# Interface.net
KiCad netlist of a schematic drawn in Altium Designer
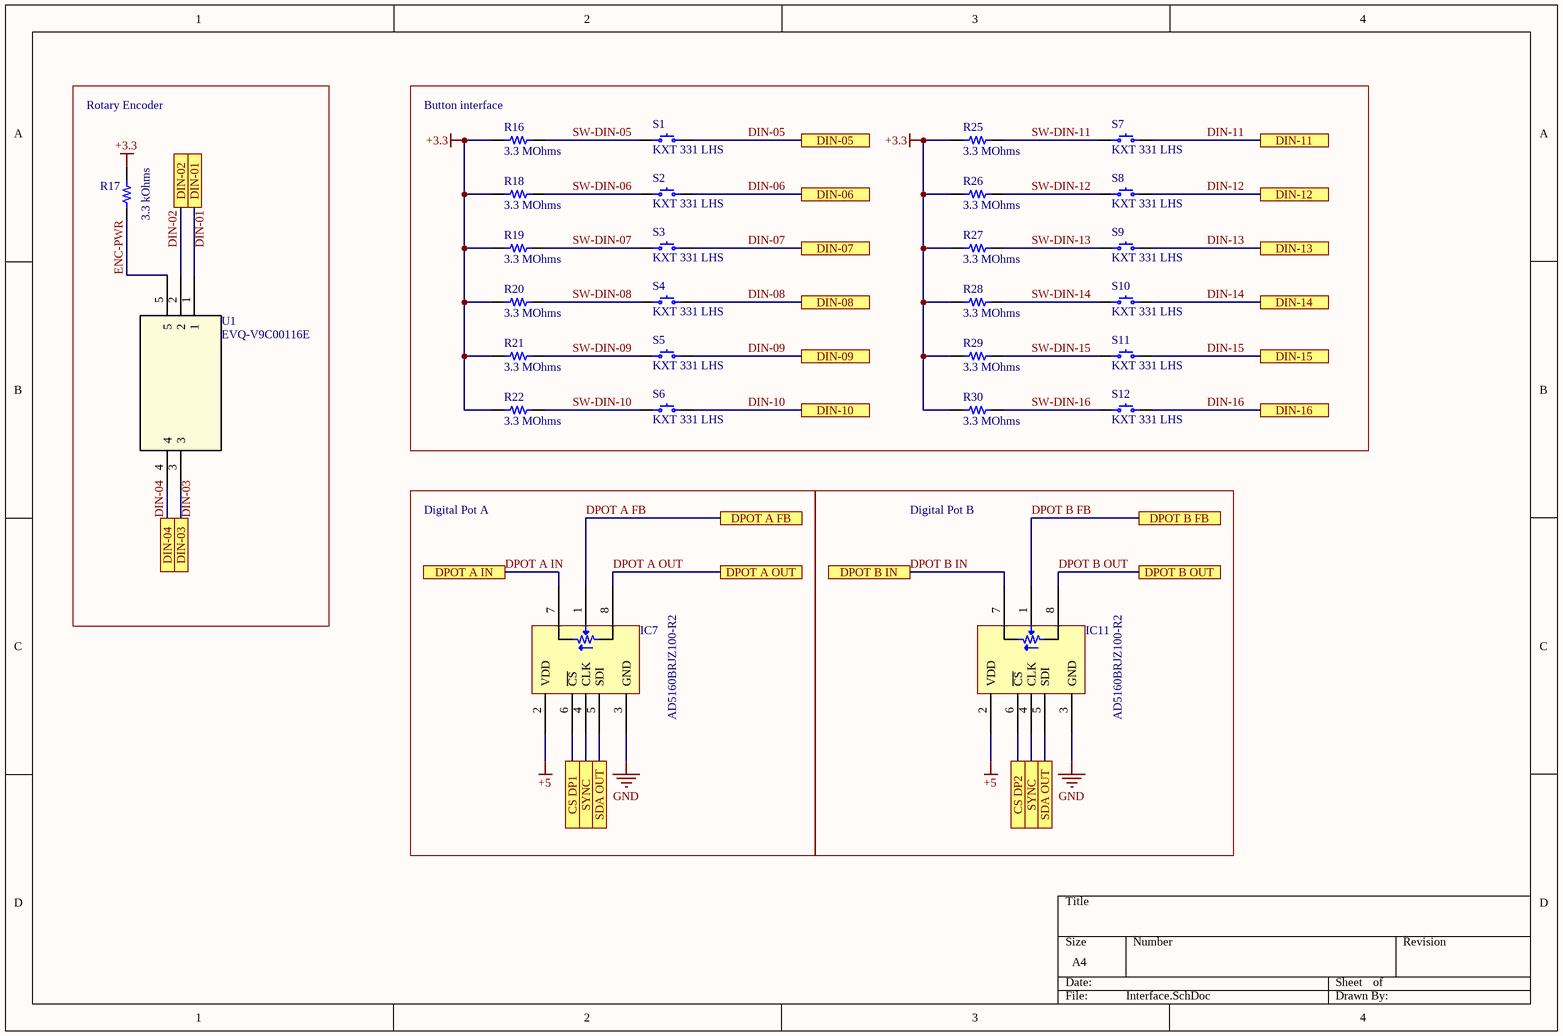
[diagram p0: Interface.SchDoc]

(export (version "E")
  (design (tool "Eeschema 10.0.6"))
  (components
    (comp (ref "IC7")
      (value "AD5160BRJZ100-R2")
      (footprint "ANALOG SOT-23-8 RJ-8")
      (description "IC DGTL POT 100KOHM 256TAP SOT23")
      (fields (field (name "MANUFACTURER") "Analog Devices Inc.") (field (name "TOLERANCE") "±15%"))
      (libsource (lib "Celestial Altium Library - altium_library(1)") (part "ANALOG AD5160"))
    )
    (comp (ref "IC11")
      (value "AD5160BRJZ100-R2")
      (footprint "ANALOG SOT-23-8 RJ-8")
      (description "IC DGTL POT 100KOHM 256TAP SOT23")
      (fields (field (name "MANUFACTURER") "Analog Devices Inc.") (field (name "TOLERANCE") "±15%"))
      (libsource (lib "Celestial Altium Library - altium_library(1)") (part "ANALOG AD5160"))
    )
    (comp (ref "R16")
      (value "3.3 MOhms")
      (footprint "RES 1206_3216")
      (description "RES 3.3M OHM 0.1% 1/4W 1206")
      (fields (field (name "PART NUMBER") "RG3216P-3304-B-T1") (field (name "MANUFACTURER") "Susumu"))
      (libsource (lib "Celestial Altium Library - altium_library(1)") (part "Resistor"))
    )
    (comp (ref "R17")
      (value "3.3 kOhms")
      (footprint "RES 1206_3216")
      (description "RES SMD 3.3K OHM 0.1% 1/4W 1206")
      (fields
        (field (name "PART NUMBER") "ERA-8APB332V")
        (field (name "MANUFACTURER") "Panasonic Electronic Components")
      )
      (libsource (lib "Celestial Altium Library - altium_library(1)") (part "Resistor"))
    )
    (comp (ref "R18")
      (value "3.3 MOhms")
      (footprint "RES 1206_3216")
      (description "RES 3.3M OHM 0.1% 1/4W 1206")
      (fields (field (name "PART NUMBER") "RG3216P-3304-B-T1") (field (name "MANUFACTURER") "Susumu"))
      (libsource (lib "Celestial Altium Library - altium_library(1)") (part "Resistor"))
    )
    (comp (ref "R19")
      (value "3.3 MOhms")
      (footprint "RES 1206_3216")
      (description "RES 3.3M OHM 0.1% 1/4W 1206")
      (fields (field (name "PART NUMBER") "RG3216P-3304-B-T1") (field (name "MANUFACTURER") "Susumu"))
      (libsource (lib "Celestial Altium Library - altium_library(1)") (part "Resistor"))
    )
    (comp (ref "R20")
      (value "3.3 MOhms")
      (footprint "RES 1206_3216")
      (description "RES 3.3M OHM 0.1% 1/4W 1206")
      (fields (field (name "PART NUMBER") "RG3216P-3304-B-T1") (field (name "MANUFACTURER") "Susumu"))
      (libsource (lib "Celestial Altium Library - altium_library(1)") (part "Resistor"))
    )
    (comp (ref "R21")
      (value "3.3 MOhms")
      (footprint "RES 1206_3216")
      (description "RES 3.3M OHM 0.1% 1/4W 1206")
      (fields (field (name "PART NUMBER") "RG3216P-3304-B-T1") (field (name "MANUFACTURER") "Susumu"))
      (libsource (lib "Celestial Altium Library - altium_library(1)") (part "Resistor"))
    )
    (comp (ref "R22")
      (value "3.3 MOhms")
      (footprint "RES 1206_3216")
      (description "RES 3.3M OHM 0.1% 1/4W 1206")
      (fields (field (name "PART NUMBER") "RG3216P-3304-B-T1") (field (name "MANUFACTURER") "Susumu"))
      (libsource (lib "Celestial Altium Library - altium_library(1)") (part "Resistor"))
    )
    (comp (ref "R25")
      (value "3.3 MOhms")
      (footprint "RES 1206_3216")
      (description "RES 3.3M OHM 0.1% 1/4W 1206")
      (fields (field (name "PART NUMBER") "RG3216P-3304-B-T1") (field (name "MANUFACTURER") "Susumu"))
      (libsource (lib "Celestial Altium Library - altium_library(1)") (part "Resistor"))
    )
    (comp (ref "R26")
      (value "3.3 MOhms")
      (footprint "RES 1206_3216")
      (description "RES 3.3M OHM 0.1% 1/4W 1206")
      (fields (field (name "PART NUMBER") "RG3216P-3304-B-T1") (field (name "MANUFACTURER") "Susumu"))
      (libsource (lib "Celestial Altium Library - altium_library(1)") (part "Resistor"))
    )
    (comp (ref "R27")
      (value "3.3 MOhms")
      (footprint "RES 1206_3216")
      (description "RES 3.3M OHM 0.1% 1/4W 1206")
      (fields (field (name "PART NUMBER") "RG3216P-3304-B-T1") (field (name "MANUFACTURER") "Susumu"))
      (libsource (lib "Celestial Altium Library - altium_library(1)") (part "Resistor"))
    )
    (comp (ref "R28")
      (value "3.3 MOhms")
      (footprint "RES 1206_3216")
      (description "RES 3.3M OHM 0.1% 1/4W 1206")
      (fields (field (name "PART NUMBER") "RG3216P-3304-B-T1") (field (name "MANUFACTURER") "Susumu"))
      (libsource (lib "Celestial Altium Library - altium_library(1)") (part "Resistor"))
    )
    (comp (ref "R29")
      (value "3.3 MOhms")
      (footprint "RES 1206_3216")
      (description "RES 3.3M OHM 0.1% 1/4W 1206")
      (fields (field (name "PART NUMBER") "RG3216P-3304-B-T1") (field (name "MANUFACTURER") "Susumu"))
      (libsource (lib "Celestial Altium Library - altium_library(1)") (part "Resistor"))
    )
    (comp (ref "R30")
      (value "3.3 MOhms")
      (footprint "RES 1206_3216")
      (description "RES 3.3M OHM 0.1% 1/4W 1206")
      (fields (field (name "PART NUMBER") "RG3216P-3304-B-T1") (field (name "MANUFACTURER") "Susumu"))
      (libsource (lib "Celestial Altium Library - altium_library(1)") (part "Resistor"))
    )
    (comp (ref "S1")
      (value "KXT 331 LHS")
      (footprint "C&K KXT3")
      (description "SWITCH TACTILE SPST-NO 0.02A 15V")
      (fields (field (name "MANUFACTURER") "C&K"))
      (libsource (lib "Celestial Altium Library - altium_library(1)") (part "SPST-NO 2 PIN"))
    )
    (comp (ref "S2")
      (value "KXT 331 LHS")
      (footprint "C&K KXT3")
      (description "SWITCH TACTILE SPST-NO 0.02A 15V")
      (fields (field (name "MANUFACTURER") "C&K"))
      (libsource (lib "Celestial Altium Library - altium_library(1)") (part "SPST-NO 2 PIN"))
    )
    (comp (ref "S3")
      (value "KXT 331 LHS")
      (footprint "C&K KXT3")
      (description "SWITCH TACTILE SPST-NO 0.02A 15V")
      (fields (field (name "MANUFACTURER") "C&K"))
      (libsource (lib "Celestial Altium Library - altium_library(1)") (part "SPST-NO 2 PIN"))
    )
    (comp (ref "S4")
      (value "KXT 331 LHS")
      (footprint "C&K KXT3")
      (description "SWITCH TACTILE SPST-NO 0.02A 15V")
      (fields (field (name "MANUFACTURER") "C&K"))
      (libsource (lib "Celestial Altium Library - altium_library(1)") (part "SPST-NO 2 PIN"))
    )
    (comp (ref "S5")
      (value "KXT 331 LHS")
      (footprint "C&K KXT3")
      (description "SWITCH TACTILE SPST-NO 0.02A 15V")
      (fields (field (name "MANUFACTURER") "C&K"))
      (libsource (lib "Celestial Altium Library - altium_library(1)") (part "SPST-NO 2 PIN"))
    )
    (comp (ref "S6")
      (value "KXT 331 LHS")
      (footprint "C&K KXT3")
      (description "SWITCH TACTILE SPST-NO 0.02A 15V")
      (fields (field (name "MANUFACTURER") "C&K"))
      (libsource (lib "Celestial Altium Library - altium_library(1)") (part "SPST-NO 2 PIN"))
    )
    (comp (ref "S7")
      (value "KXT 331 LHS")
      (footprint "C&K KXT3")
      (description "SWITCH TACTILE SPST-NO 0.02A 15V")
      (fields (field (name "MANUFACTURER") "C&K"))
      (libsource (lib "Celestial Altium Library - altium_library(1)") (part "SPST-NO 2 PIN"))
    )
    (comp (ref "S8")
      (value "KXT 331 LHS")
      (footprint "C&K KXT3")
      (description "SWITCH TACTILE SPST-NO 0.02A 15V")
      (fields (field (name "MANUFACTURER") "C&K"))
      (libsource (lib "Celestial Altium Library - altium_library(1)") (part "SPST-NO 2 PIN"))
    )
    (comp (ref "S9")
      (value "KXT 331 LHS")
      (footprint "C&K KXT3")
      (description "SWITCH TACTILE SPST-NO 0.02A 15V")
      (fields (field (name "MANUFACTURER") "C&K"))
      (libsource (lib "Celestial Altium Library - altium_library(1)") (part "SPST-NO 2 PIN"))
    )
    (comp (ref "S10")
      (value "KXT 331 LHS")
      (footprint "C&K KXT3")
      (description "SWITCH TACTILE SPST-NO 0.02A 15V")
      (fields (field (name "MANUFACTURER") "C&K"))
      (libsource (lib "Celestial Altium Library - altium_library(1)") (part "SPST-NO 2 PIN"))
    )
    (comp (ref "S11")
      (value "KXT 331 LHS")
      (footprint "C&K KXT3")
      (description "SWITCH TACTILE SPST-NO 0.02A 15V")
      (fields (field (name "MANUFACTURER") "C&K"))
      (libsource (lib "Celestial Altium Library - altium_library(1)") (part "SPST-NO 2 PIN"))
    )
    (comp (ref "S12")
      (value "KXT 331 LHS")
      (footprint "C&K KXT3")
      (description "SWITCH TACTILE SPST-NO 0.02A 15V")
      (fields (field (name "MANUFACTURER") "C&K"))
      (libsource (lib "Celestial Altium Library - altium_library(1)") (part "SPST-NO 2 PIN"))
    )
    (comp (ref "U1")
      (value "EVQ-V9C00116E")
      (footprint "SW_EVQ-V9C00116E_PAN")
      (description "No Description Available")
      (libsource (lib "EVQ-V9C00116E") (part "EVQ-V9C00116E"))
    )
  )
  (nets
    (net (code "1") (name "+3.3") (class "Default")
      (node (ref "R16") (pin "1") (pinfunction "1_1") (pintype "passive"))
      (node (ref "R17") (pin "2") (pinfunction "2_2") (pintype "passive"))
      (node (ref "R18") (pin "1") (pinfunction "1_1") (pintype "passive"))
      (node (ref "R19") (pin "1") (pinfunction "1_1") (pintype "passive"))
      (node (ref "R20") (pin "1") (pinfunction "1_1") (pintype "passive"))
      (node (ref "R21") (pin "1") (pinfunction "1_1") (pintype "passive"))
      (node (ref "R22") (pin "1") (pinfunction "1_1") (pintype "passive"))
      (node (ref "R25") (pin "1") (pinfunction "1_1") (pintype "passive"))
      (node (ref "R26") (pin "1") (pinfunction "1_1") (pintype "passive"))
      (node (ref "R27") (pin "1") (pinfunction "1_1") (pintype "passive"))
      (node (ref "R28") (pin "1") (pinfunction "1_1") (pintype "passive"))
      (node (ref "R29") (pin "1") (pinfunction "1_1") (pintype "passive"))
      (node (ref "R30") (pin "1") (pinfunction "1_1") (pintype "passive"))
    )
    (net (code "2") (name "+5") (class "Default")
      (node (ref "IC11") (pin "2") (pinfunction "VDD_2") (pintype "passive"))
      (node (ref "IC7") (pin "2") (pinfunction "VDD_2") (pintype "passive"))
    )
    (net (code "3") (name "/CS DP1") (class "Default")
      (node (ref "IC7") (pin "6") (pinfunction "~{CS}_6") (pintype "passive"))
    )
    (net (code "4") (name "/CS DP2") (class "Default")
      (node (ref "IC11") (pin "6") (pinfunction "~{CS}_6") (pintype "passive"))
    )
    (net (code "5") (name "/DIN-01") (class "Default")
      (node (ref "U1") (pin "1") (pinfunction "1_1") (pintype "passive"))
    )
    (net (code "6") (name "/DIN-02") (class "Default")
      (node (ref "U1") (pin "2") (pinfunction "2_2") (pintype "passive"))
    )
    (net (code "7") (name "/DIN-03") (class "Default")
      (node (ref "U1") (pin "3") (pinfunction "3_3") (pintype "passive"))
    )
    (net (code "8") (name "/DIN-04") (class "Default")
      (node (ref "U1") (pin "4") (pinfunction "4_4") (pintype "passive"))
    )
    (net (code "9") (name "/DIN-05") (class "Default")
      (node (ref "S1") (pin "2") (pinfunction "2_2") (pintype "passive"))
    )
    (net (code "10") (name "/DIN-06") (class "Default")
      (node (ref "S2") (pin "2") (pinfunction "2_2") (pintype "passive"))
    )
    (net (code "11") (name "/DIN-07") (class "Default")
      (node (ref "S3") (pin "2") (pinfunction "2_2") (pintype "passive"))
    )
    (net (code "12") (name "/DIN-08") (class "Default")
      (node (ref "S4") (pin "2") (pinfunction "2_2") (pintype "passive"))
    )
    (net (code "13") (name "/DIN-09") (class "Default")
      (node (ref "S5") (pin "2") (pinfunction "2_2") (pintype "passive"))
    )
    (net (code "14") (name "/DIN-10") (class "Default")
      (node (ref "S6") (pin "2") (pinfunction "2_2") (pintype "passive"))
    )
    (net (code "15") (name "/DIN-11") (class "Default")
      (node (ref "S7") (pin "2") (pinfunction "2_2") (pintype "passive"))
    )
    (net (code "16") (name "/DIN-12") (class "Default")
      (node (ref "S8") (pin "2") (pinfunction "2_2") (pintype "passive"))
    )
    (net (code "17") (name "/DIN-13") (class "Default")
      (node (ref "S9") (pin "2") (pinfunction "2_2") (pintype "passive"))
    )
    (net (code "18") (name "/DIN-14") (class "Default")
      (node (ref "S10") (pin "2") (pinfunction "2_2") (pintype "passive"))
    )
    (net (code "19") (name "/DIN-15") (class "Default")
      (node (ref "S11") (pin "2") (pinfunction "2_2") (pintype "passive"))
    )
    (net (code "20") (name "/DIN-16") (class "Default")
      (node (ref "S12") (pin "2") (pinfunction "2_2") (pintype "passive"))
    )
    (net (code "21") (name "/DPOT A FB") (class "Default")
      (node (ref "IC7") (pin "1") (pinfunction "W_1") (pintype "passive"))
    )
    (net (code "22") (name "/DPOT A IN") (class "Default")
      (node (ref "IC7") (pin "7") (pinfunction "A_7") (pintype "passive"))
    )
    (net (code "23") (name "/DPOT A OUT") (class "Default")
      (node (ref "IC7") (pin "8") (pinfunction "B_8") (pintype "passive"))
    )
    (net (code "24") (name "/DPOT B FB") (class "Default")
      (node (ref "IC11") (pin "1") (pinfunction "W_1") (pintype "passive"))
    )
    (net (code "25") (name "/DPOT B IN") (class "Default")
      (node (ref "IC11") (pin "7") (pinfunction "A_7") (pintype "passive"))
    )
    (net (code "26") (name "/DPOT B OUT") (class "Default")
      (node (ref "IC11") (pin "8") (pinfunction "B_8") (pintype "passive"))
    )
    (net (code "27") (name "/ENC-PWR") (class "Default")
      (node (ref "R17") (pin "1") (pinfunction "1_1") (pintype "passive"))
      (node (ref "U1") (pin "5") (pinfunction "5_5") (pintype "passive"))
    )
    (net (code "28") (name "/SDA OUT") (class "Default")
      (node (ref "IC11") (pin "5") (pinfunction "SDI_5") (pintype "passive"))
      (node (ref "IC7") (pin "5") (pinfunction "SDI_5") (pintype "passive"))
    )
    (net (code "29") (name "/SW-DIN-05") (class "Default")
      (node (ref "R16") (pin "2") (pinfunction "2_2") (pintype "passive"))
      (node (ref "S1") (pin "1") (pinfunction "1_1") (pintype "passive"))
    )
    (net (code "30") (name "/SW-DIN-06") (class "Default")
      (node (ref "R18") (pin "2") (pinfunction "2_2") (pintype "passive"))
      (node (ref "S2") (pin "1") (pinfunction "1_1") (pintype "passive"))
    )
    (net (code "31") (name "/SW-DIN-07") (class "Default")
      (node (ref "R19") (pin "2") (pinfunction "2_2") (pintype "passive"))
      (node (ref "S3") (pin "1") (pinfunction "1_1") (pintype "passive"))
    )
    (net (code "32") (name "/SW-DIN-08") (class "Default")
      (node (ref "R20") (pin "2") (pinfunction "2_2") (pintype "passive"))
      (node (ref "S4") (pin "1") (pinfunction "1_1") (pintype "passive"))
    )
    (net (code "33") (name "/SW-DIN-09") (class "Default")
      (node (ref "R21") (pin "2") (pinfunction "2_2") (pintype "passive"))
      (node (ref "S5") (pin "1") (pinfunction "1_1") (pintype "passive"))
    )
    (net (code "34") (name "/SW-DIN-10") (class "Default")
      (node (ref "R22") (pin "2") (pinfunction "2_2") (pintype "passive"))
      (node (ref "S6") (pin "1") (pinfunction "1_1") (pintype "passive"))
    )
    (net (code "35") (name "/SW-DIN-11") (class "Default")
      (node (ref "R25") (pin "2") (pinfunction "2_2") (pintype "passive"))
      (node (ref "S7") (pin "1") (pinfunction "1_1") (pintype "passive"))
    )
    (net (code "36") (name "/SW-DIN-12") (class "Default")
      (node (ref "R26") (pin "2") (pinfunction "2_2") (pintype "passive"))
      (node (ref "S8") (pin "1") (pinfunction "1_1") (pintype "passive"))
    )
    (net (code "37") (name "/SW-DIN-13") (class "Default")
      (node (ref "R27") (pin "2") (pinfunction "2_2") (pintype "passive"))
      (node (ref "S9") (pin "1") (pinfunction "1_1") (pintype "passive"))
    )
    (net (code "38") (name "/SW-DIN-14") (class "Default")
      (node (ref "R28") (pin "2") (pinfunction "2_2") (pintype "passive"))
      (node (ref "S10") (pin "1") (pinfunction "1_1") (pintype "passive"))
    )
    (net (code "39") (name "/SW-DIN-15") (class "Default")
      (node (ref "R29") (pin "2") (pinfunction "2_2") (pintype "passive"))
      (node (ref "S11") (pin "1") (pinfunction "1_1") (pintype "passive"))
    )
    (net (code "40") (name "/SW-DIN-16") (class "Default")
      (node (ref "R30") (pin "2") (pinfunction "2_2") (pintype "passive"))
      (node (ref "S12") (pin "1") (pinfunction "1_1") (pintype "passive"))
    )
    (net (code "41") (name "/SYNC") (class "Default")
      (node (ref "IC11") (pin "4") (pinfunction "CLK_4") (pintype "passive"))
      (node (ref "IC7") (pin "4") (pinfunction "CLK_4") (pintype "passive"))
    )
    (net (code "42") (name "GND") (class "Default")
      (node (ref "IC11") (pin "3") (pinfunction "GND_3") (pintype "passive"))
      (node (ref "IC7") (pin "3") (pinfunction "GND_3") (pintype "passive"))
    )
  )
)
